# LHR_Encoder_Board.net
KiCad netlist of a schematic drawn in Altium Designer
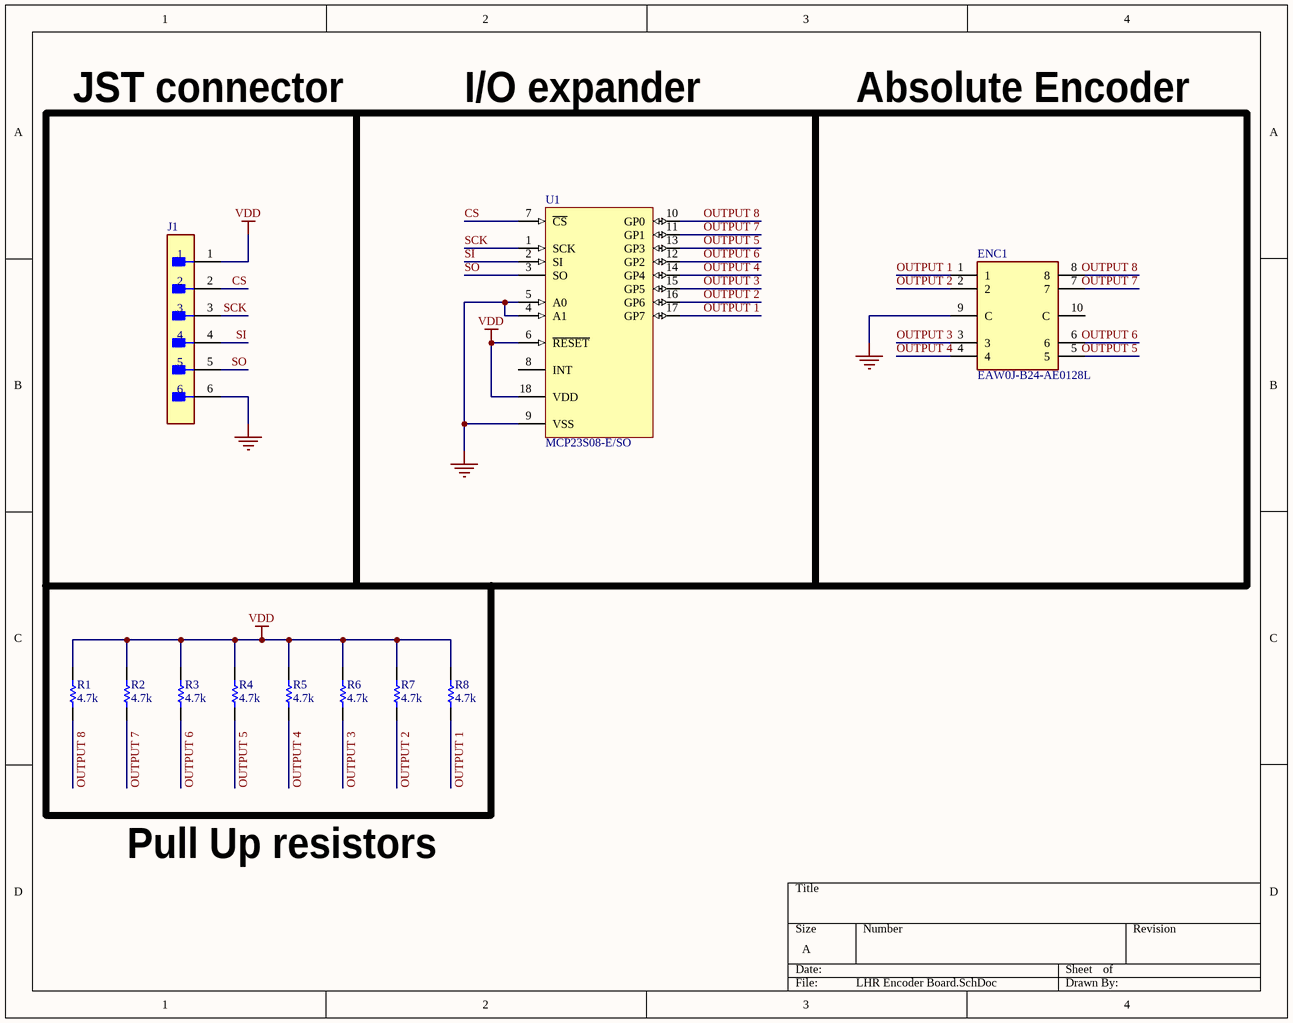
[diagram p0: LHR Encoder Board.SchDoc]

(export (version "E")
  (design (tool "Eeschema 10.0.6"))
  (components
    (comp (ref "ENC1")
      (value "EAW0J-B24-AE0128L")
      (footprint "FP-EAW0J-B24-AE0128L-MFG")
      (description "ROTARY ENCODER MECHANICAL 128PPR")
      (libsource (lib "Altium Content Vault") (part "a768c1b3463e4744d380766676121f2"))
    )
    (comp (ref "J1")
      (value "S6B-XH-A (LF)(SN)")
      (footprint "FP-S6B-XH-A_LF_SN-MFG")
      (description "CONN HEADER R/A 6POS 2.5MM")
      (libsource (lib "Altium Content Vault") (part "f2cb566baf1c37ab5a3b8e90bbeafd6"))
    )
    (comp (ref "R1")
      (value "4.7k")
      (footprint "RESC1608X55X30NL15T15")
      (fields (field (name "TOLERANCE") "5%"))
      (libsource (lib "Altium Content Vault") (part "RES-2"))
    )
    (comp (ref "R2")
      (value "4.7k")
      (footprint "RESC1608X55X30NL15T15")
      (fields (field (name "TOLERANCE") "5%"))
      (libsource (lib "Altium Content Vault") (part "RES-2"))
    )
    (comp (ref "R3")
      (value "4.7k")
      (footprint "RESC1608X55X30NL15T15")
      (fields (field (name "TOLERANCE") "5%"))
      (libsource (lib "Altium Content Vault") (part "RES-2"))
    )
    (comp (ref "R4")
      (value "4.7k")
      (footprint "RESC1608X55X30NL15T15")
      (fields (field (name "TOLERANCE") "5%"))
      (libsource (lib "Altium Content Vault") (part "RES-2"))
    )
    (comp (ref "R5")
      (value "4.7k")
      (footprint "RESC1608X55X30NL15T15")
      (fields (field (name "TOLERANCE") "5%"))
      (libsource (lib "Altium Content Vault") (part "RES-2"))
    )
    (comp (ref "R6")
      (value "4.7k")
      (footprint "RESC1608X55X30NL15T15")
      (fields (field (name "TOLERANCE") "5%"))
      (libsource (lib "Altium Content Vault") (part "RES-2"))
    )
    (comp (ref "R7")
      (value "4.7k")
      (footprint "RESC1608X55X30NL15T15")
      (fields (field (name "TOLERANCE") "5%"))
      (libsource (lib "Altium Content Vault") (part "RES-2"))
    )
    (comp (ref "R8")
      (value "4.7k")
      (footprint "RESC1608X55X30NL15T15")
      (fields (field (name "TOLERANCE") "5%"))
      (libsource (lib "Altium Content Vault") (part "RES-2"))
    )
    (comp (ref "U1")
      (value "MCP23S08-E/SO")
      (footprint "SOIC-SO18_N")
      (description "8-Bit I/O Expander with Serial Interface, 18-Pin SOIC, Extended Temperature")
      (libsource (lib "Altium Content Vault") (part "PR-BUSIC-MCP23S08-18"))
    )
  )
  (nets
    (net (code "1") (name "/CS") (class "Default")
      (node (ref "J1") (pin "2") (pinfunction "2_2") (pintype "passive"))
      (node (ref "U1") (pin "7") (pinfunction "~{CS}_7") (pintype "input"))
    )
    (net (code "2") (name "/OUTPUT 1") (class "Default")
      (node (ref "ENC1") (pin "1") (pinfunction "1_1") (pintype "passive"))
      (node (ref "R8") (pin "1") (pinfunction "1_1") (pintype "passive"))
      (node (ref "U1") (pin "17") (pinfunction "GP7_17") (pintype "bidirectional"))
    )
    (net (code "3") (name "/OUTPUT 2") (class "Default")
      (node (ref "ENC1") (pin "2") (pinfunction "2_2") (pintype "passive"))
      (node (ref "R7") (pin "1") (pinfunction "1_1") (pintype "passive"))
      (node (ref "U1") (pin "16") (pinfunction "GP6_16") (pintype "bidirectional"))
    )
    (net (code "4") (name "/OUTPUT 3") (class "Default")
      (node (ref "ENC1") (pin "3") (pinfunction "3_3") (pintype "passive"))
      (node (ref "R6") (pin "1") (pinfunction "1_1") (pintype "passive"))
      (node (ref "U1") (pin "15") (pinfunction "GP5_15") (pintype "bidirectional"))
    )
    (net (code "5") (name "/OUTPUT 4") (class "Default")
      (node (ref "ENC1") (pin "4") (pinfunction "4_4") (pintype "passive"))
      (node (ref "R5") (pin "1") (pinfunction "1_1") (pintype "passive"))
      (node (ref "U1") (pin "14") (pinfunction "GP4_14") (pintype "bidirectional"))
    )
    (net (code "6") (name "/OUTPUT 5") (class "Default")
      (node (ref "ENC1") (pin "5") (pinfunction "5_5") (pintype "passive"))
      (node (ref "R4") (pin "1") (pinfunction "1_1") (pintype "passive"))
      (node (ref "U1") (pin "13") (pinfunction "GP3_13") (pintype "bidirectional"))
    )
    (net (code "7") (name "/OUTPUT 6") (class "Default")
      (node (ref "ENC1") (pin "6") (pinfunction "6_6") (pintype "passive"))
      (node (ref "R3") (pin "1") (pinfunction "1_1") (pintype "passive"))
      (node (ref "U1") (pin "12") (pinfunction "GP2_12") (pintype "bidirectional"))
    )
    (net (code "8") (name "/OUTPUT 7") (class "Default")
      (node (ref "ENC1") (pin "7") (pinfunction "7_7") (pintype "passive"))
      (node (ref "R2") (pin "1") (pinfunction "1_1") (pintype "passive"))
      (node (ref "U1") (pin "11") (pinfunction "GP1_11") (pintype "bidirectional"))
    )
    (net (code "9") (name "/OUTPUT 8") (class "Default")
      (node (ref "ENC1") (pin "8") (pinfunction "8_8") (pintype "passive"))
      (node (ref "R1") (pin "1") (pinfunction "1_1") (pintype "passive"))
      (node (ref "U1") (pin "10") (pinfunction "GP0_10") (pintype "bidirectional"))
    )
    (net (code "10") (name "/SCK") (class "Default")
      (node (ref "J1") (pin "3") (pinfunction "3_3") (pintype "passive"))
      (node (ref "U1") (pin "1") (pinfunction "SCK_1") (pintype "input"))
    )
    (net (code "11") (name "/SI") (class "Default")
      (node (ref "J1") (pin "4") (pinfunction "4_4") (pintype "passive"))
      (node (ref "U1") (pin "2") (pinfunction "SI_2") (pintype "input"))
    )
    (net (code "12") (name "/SO") (class "Default")
      (node (ref "J1") (pin "5") (pinfunction "5_5") (pintype "passive"))
      (node (ref "U1") (pin "3") (pinfunction "SO_3") (pintype "tri_state"))
    )
    (net (code "13") (name "GND") (class "Default")
      (node (ref "ENC1") (pin "9") (pinfunction "C_9") (pintype "passive"))
      (node (ref "J1") (pin "6") (pinfunction "6_6") (pintype "passive"))
      (node (ref "U1") (pin "4") (pinfunction "A1_4") (pintype "input"))
      (node (ref "U1") (pin "5") (pinfunction "A0_5") (pintype "input"))
      (node (ref "U1") (pin "9") (pinfunction "VSS_9") (pintype "power_in"))
    )
    (net (code "14") (name "VDD") (class "Default")
      (node (ref "J1") (pin "1") (pinfunction "1_1") (pintype "passive"))
      (node (ref "R1") (pin "2") (pinfunction "2_2") (pintype "passive"))
      (node (ref "R2") (pin "2") (pinfunction "2_2") (pintype "passive"))
      (node (ref "R3") (pin "2") (pinfunction "2_2") (pintype "passive"))
      (node (ref "R4") (pin "2") (pinfunction "2_2") (pintype "passive"))
      (node (ref "R5") (pin "2") (pinfunction "2_2") (pintype "passive"))
      (node (ref "R6") (pin "2") (pinfunction "2_2") (pintype "passive"))
      (node (ref "R7") (pin "2") (pinfunction "2_2") (pintype "passive"))
      (node (ref "R8") (pin "2") (pinfunction "2_2") (pintype "passive"))
      (node (ref "U1") (pin "18") (pinfunction "VDD_18") (pintype "power_in"))
      (node (ref "U1") (pin "6") (pinfunction "~{RESET}_6") (pintype "input"))
    )
    (net (code "15") (name "unconnected-(ENC1-C-Pad10)") (class "Default")
      (node (ref "ENC1") (pin "10") (pinfunction "C_10") (pintype "passive"))
    )
    (net (code "16") (name "unconnected-(U1-INT-Pad8)") (class "Default")
      (node (ref "U1") (pin "8") (pinfunction "INT_8") (pintype "open_collector"))
    )
  )
)
